# iron-hotplate.net
KiCad netlist of a schematic drawn in EAGLE
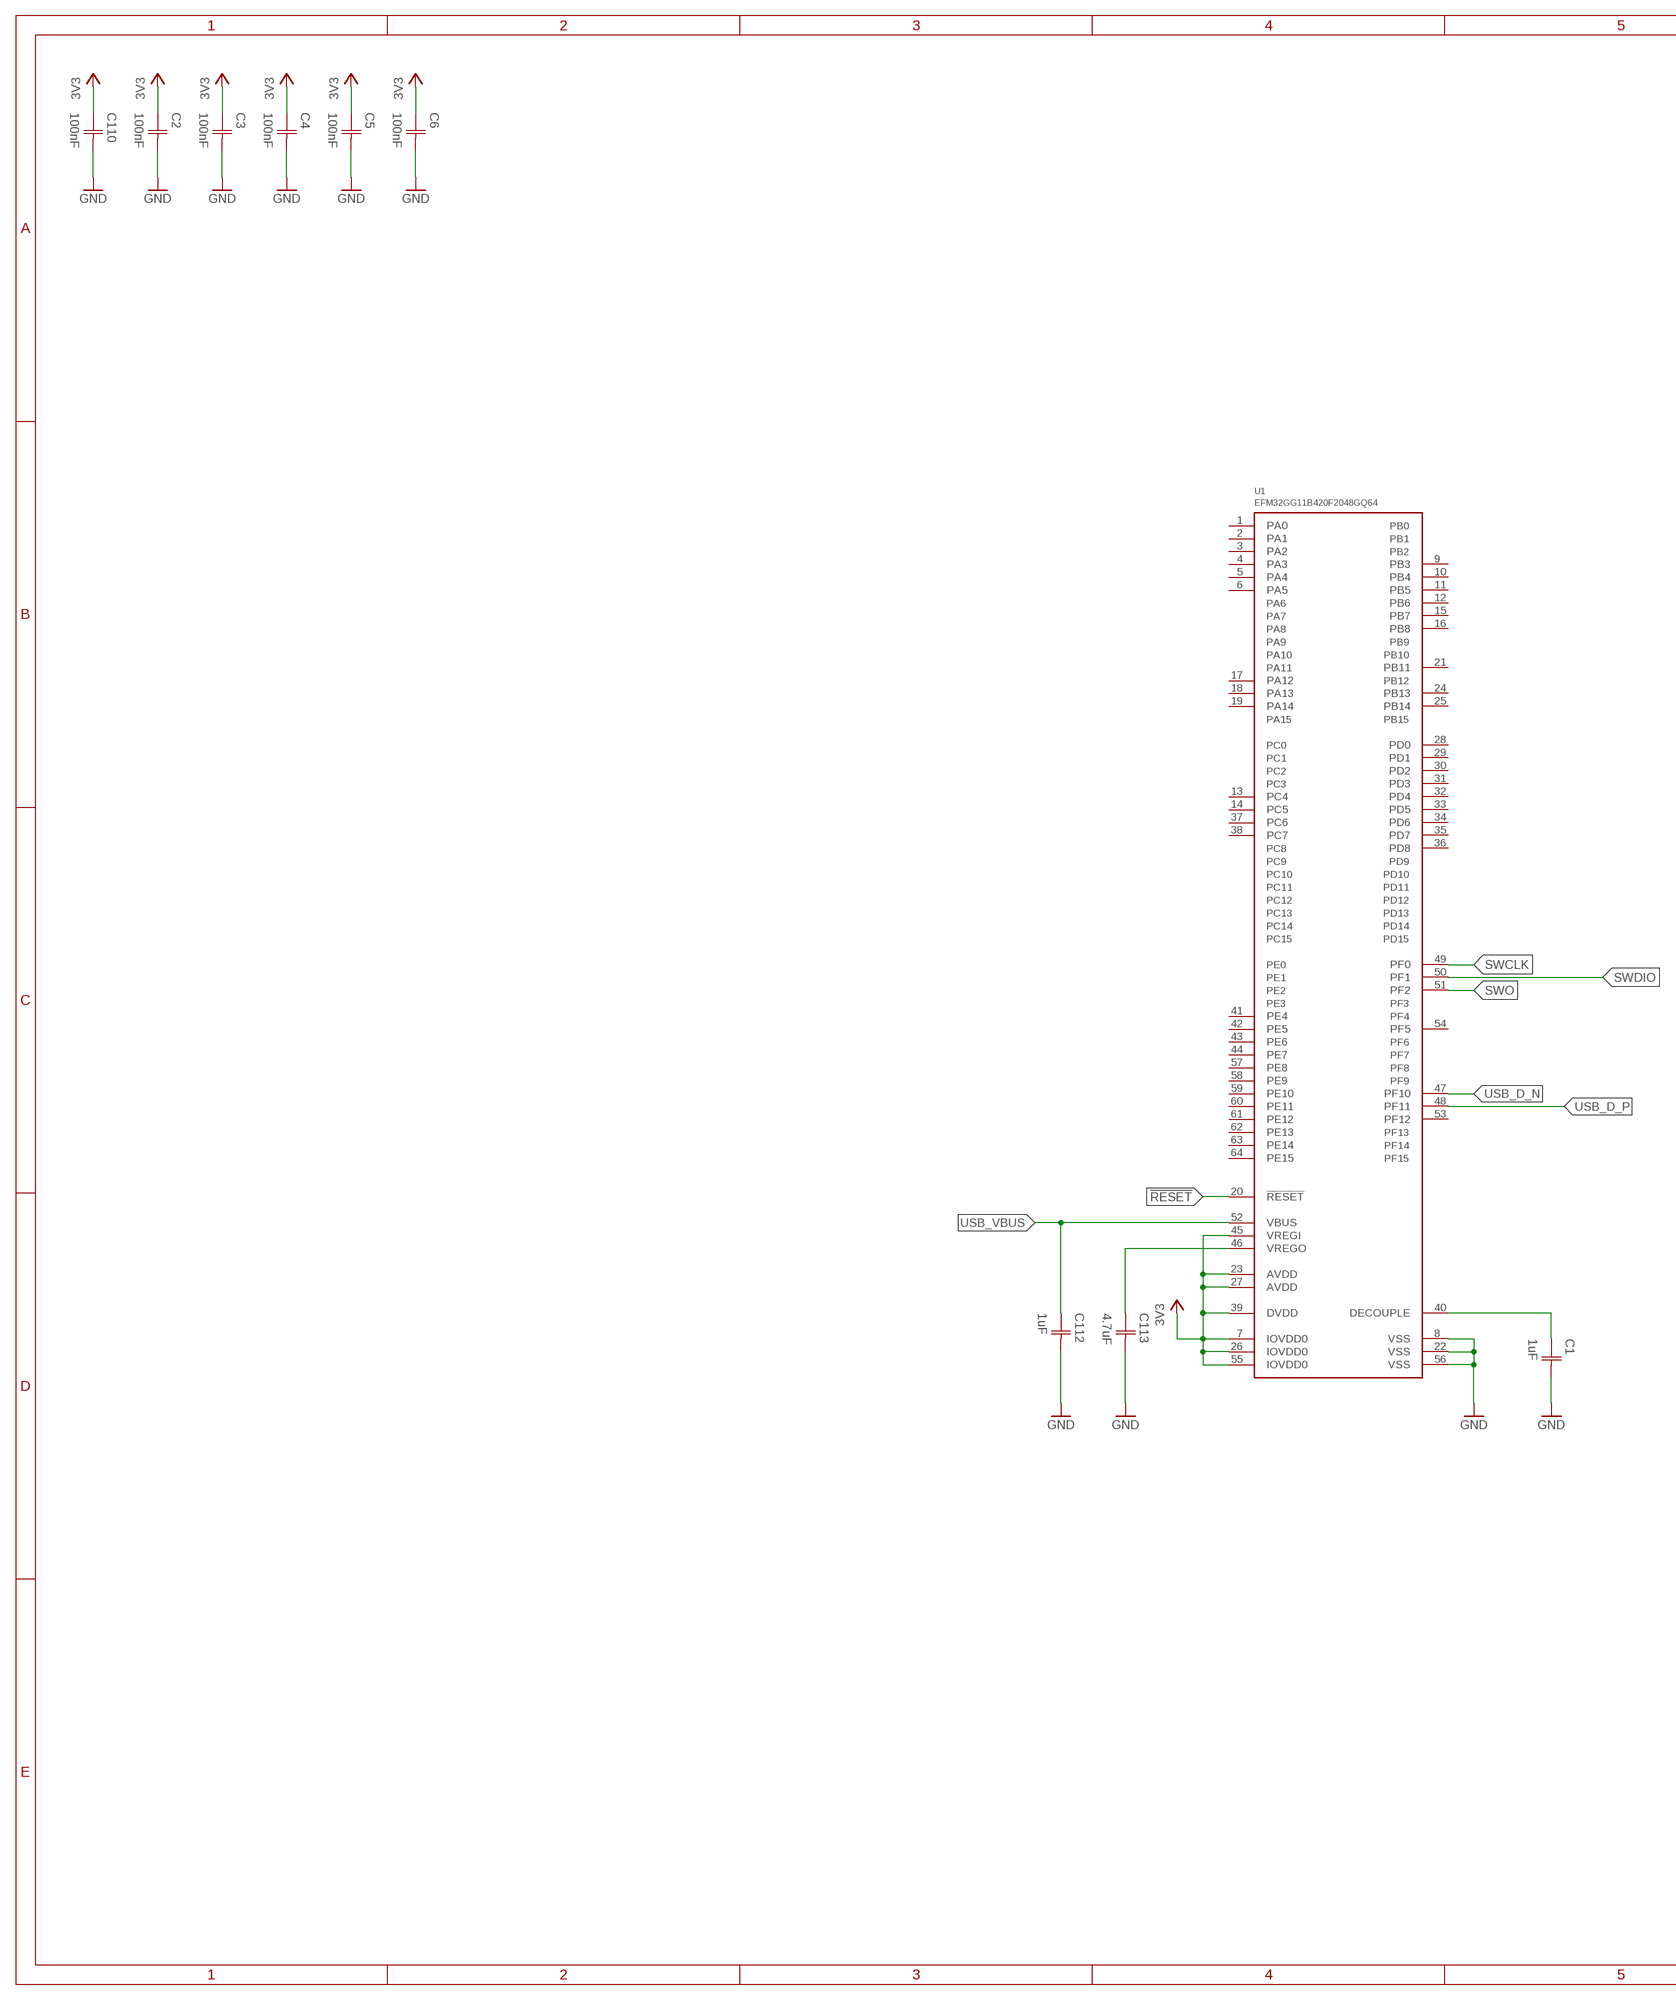
[diagram p0: schematic, sheet 1, part 1 of 2]
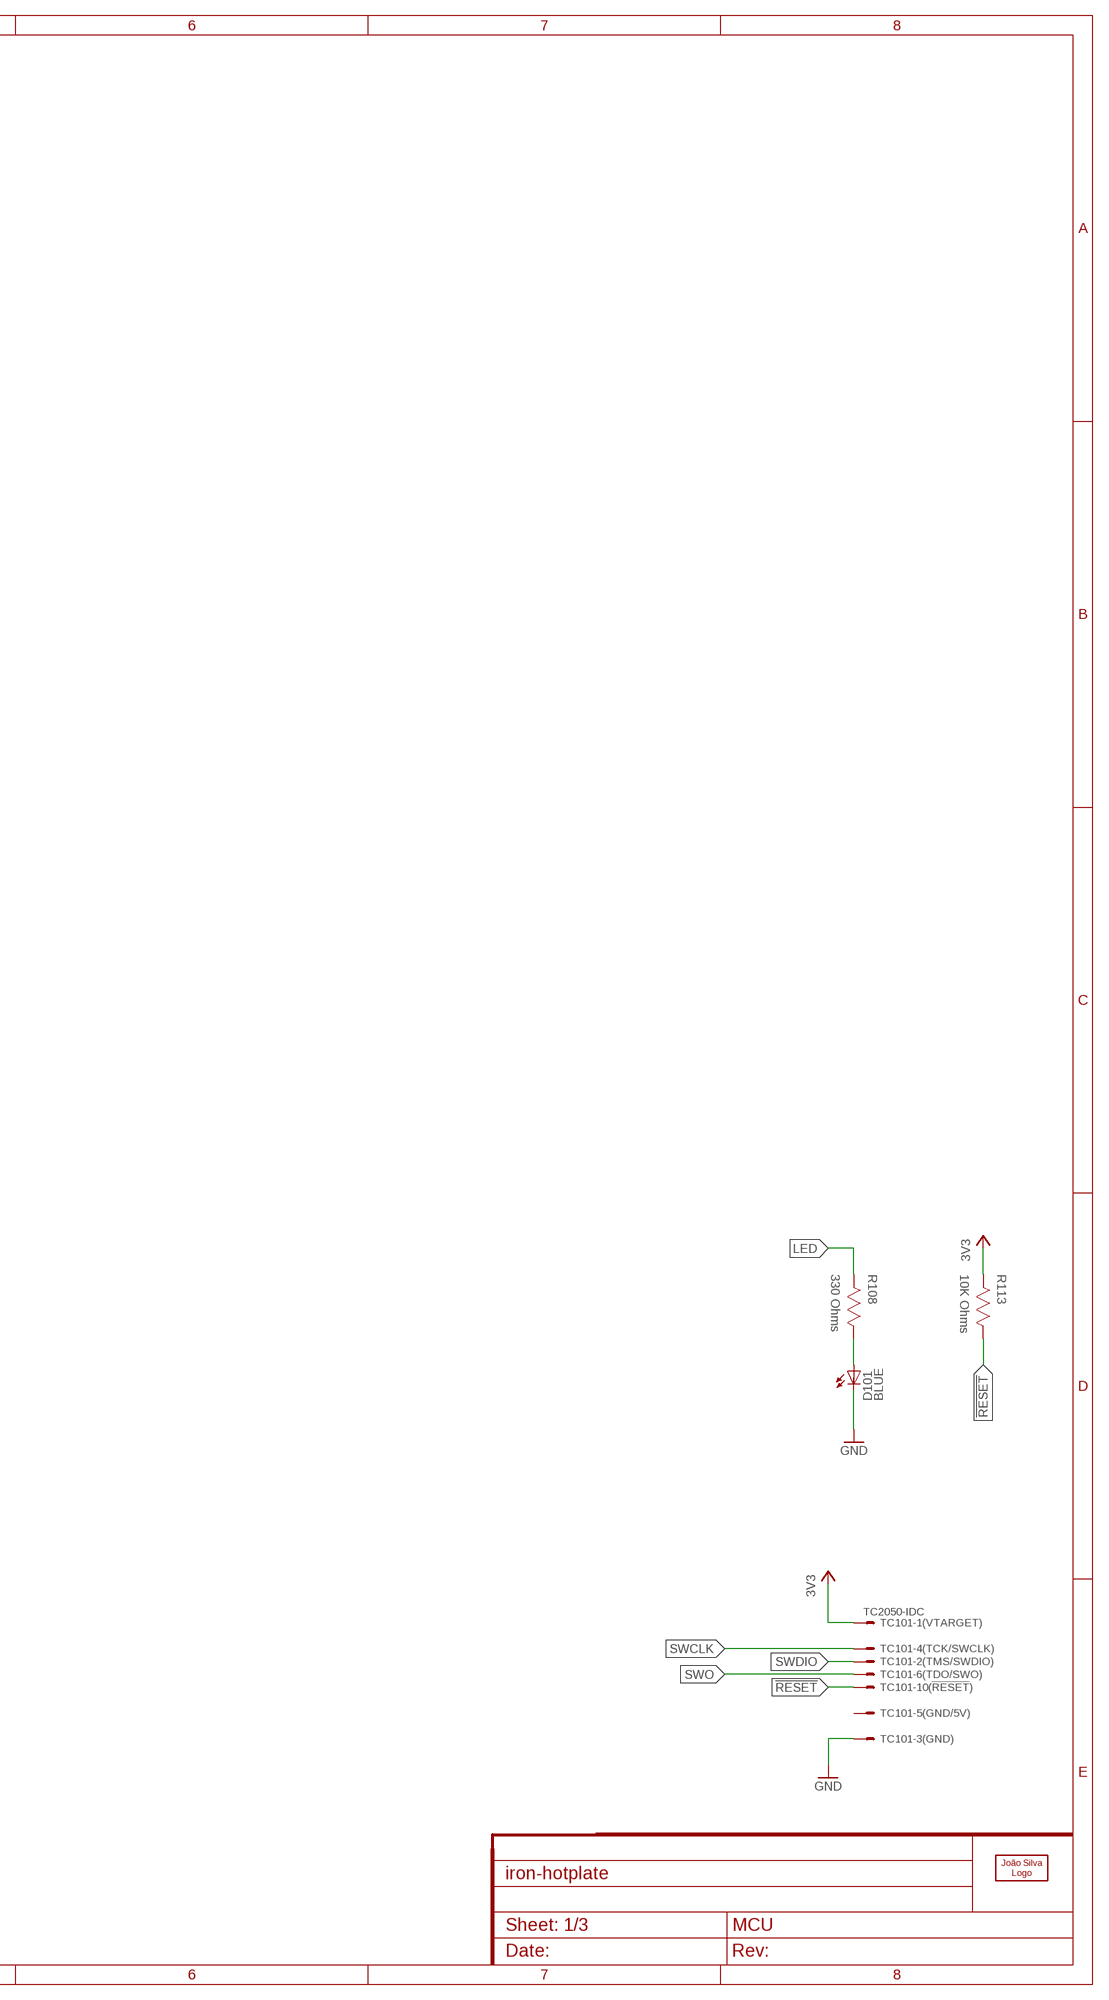
[diagram p1: schematic, sheet 1, part 2 of 2]
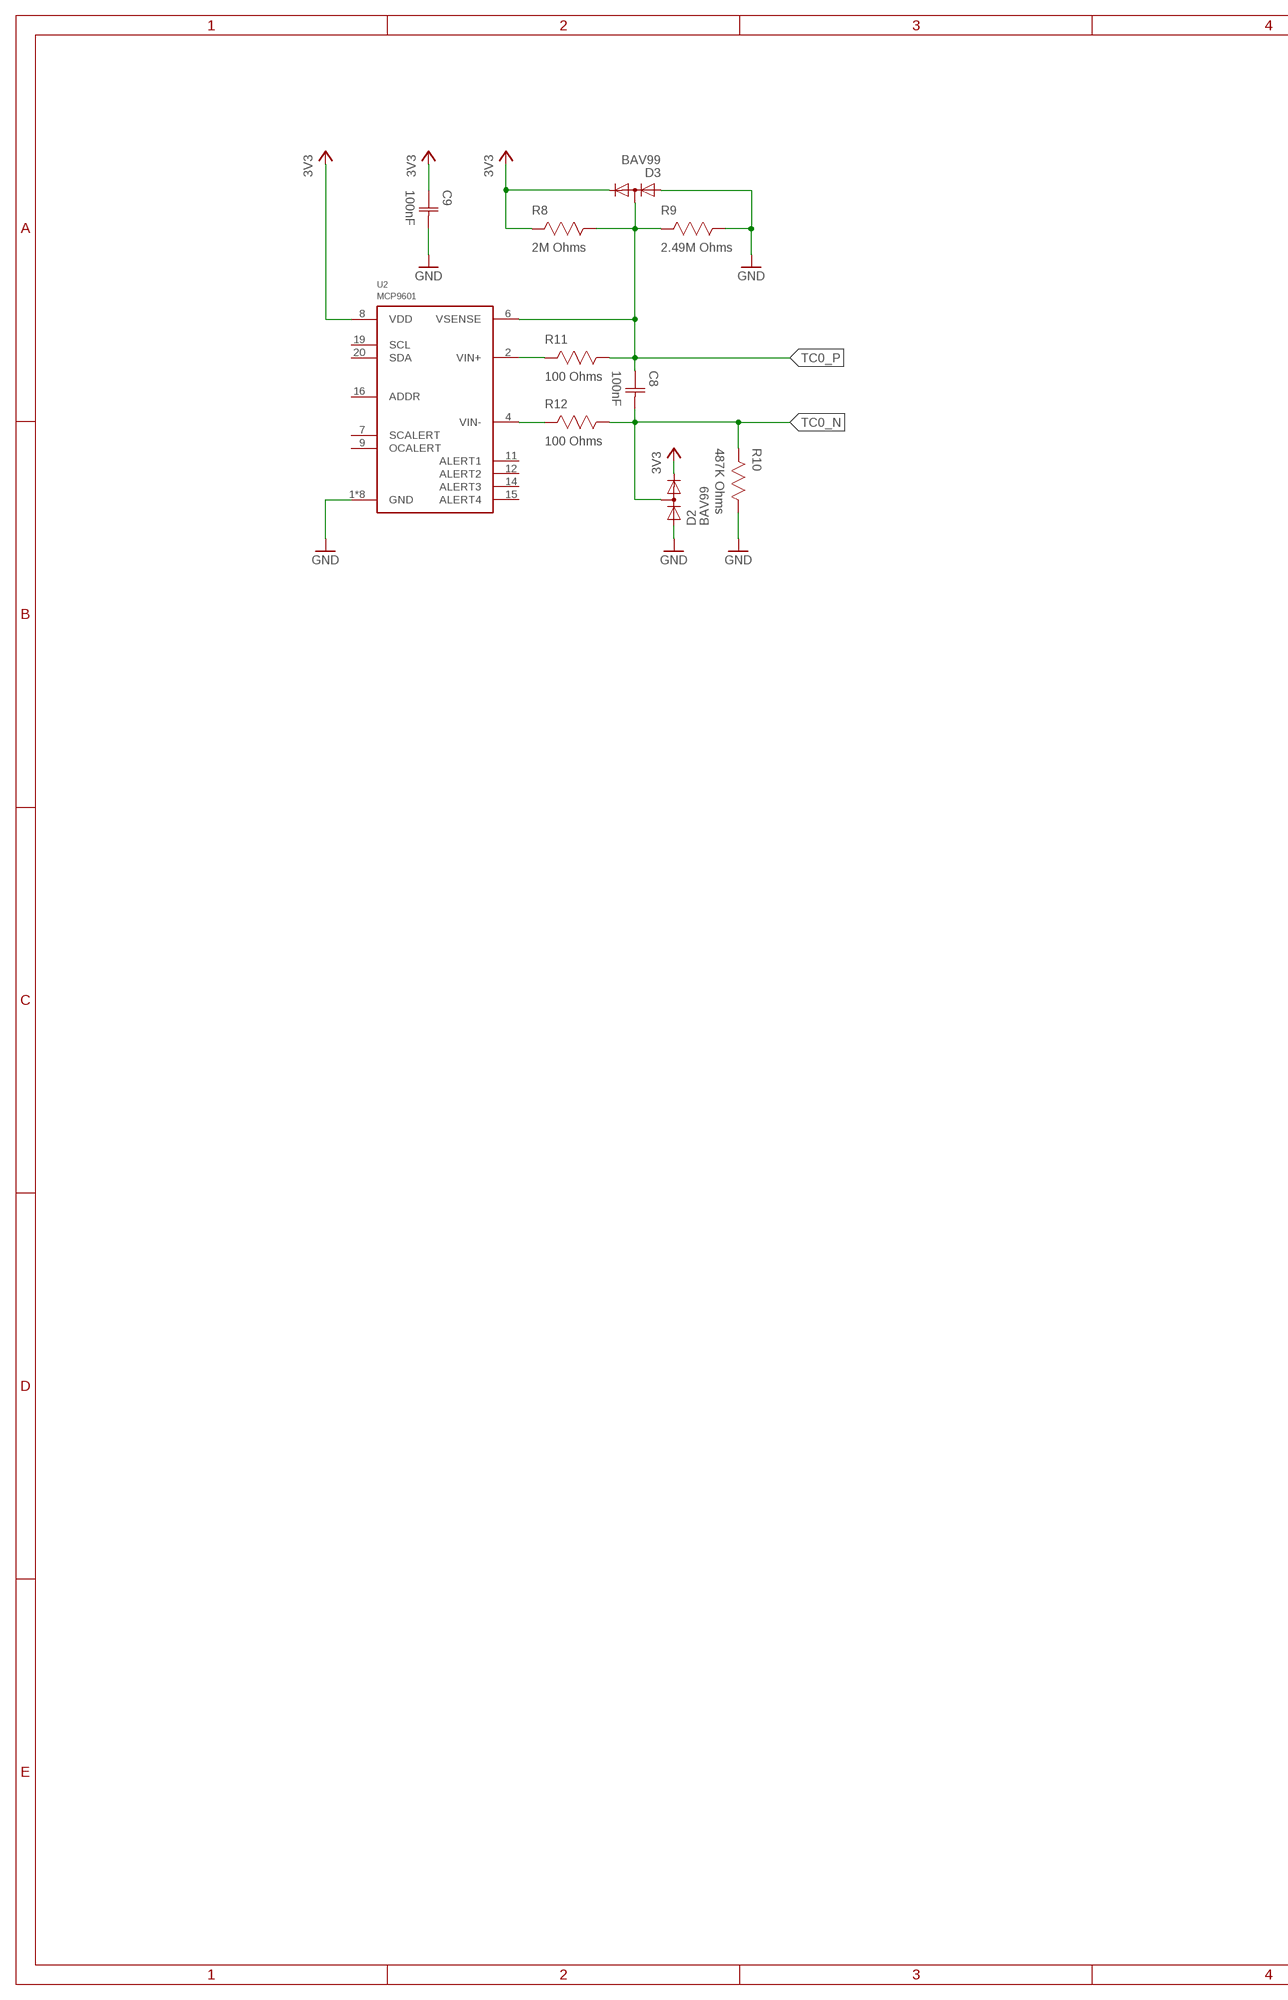
[diagram p2: schematic, sheet 2, part 1 of 2]
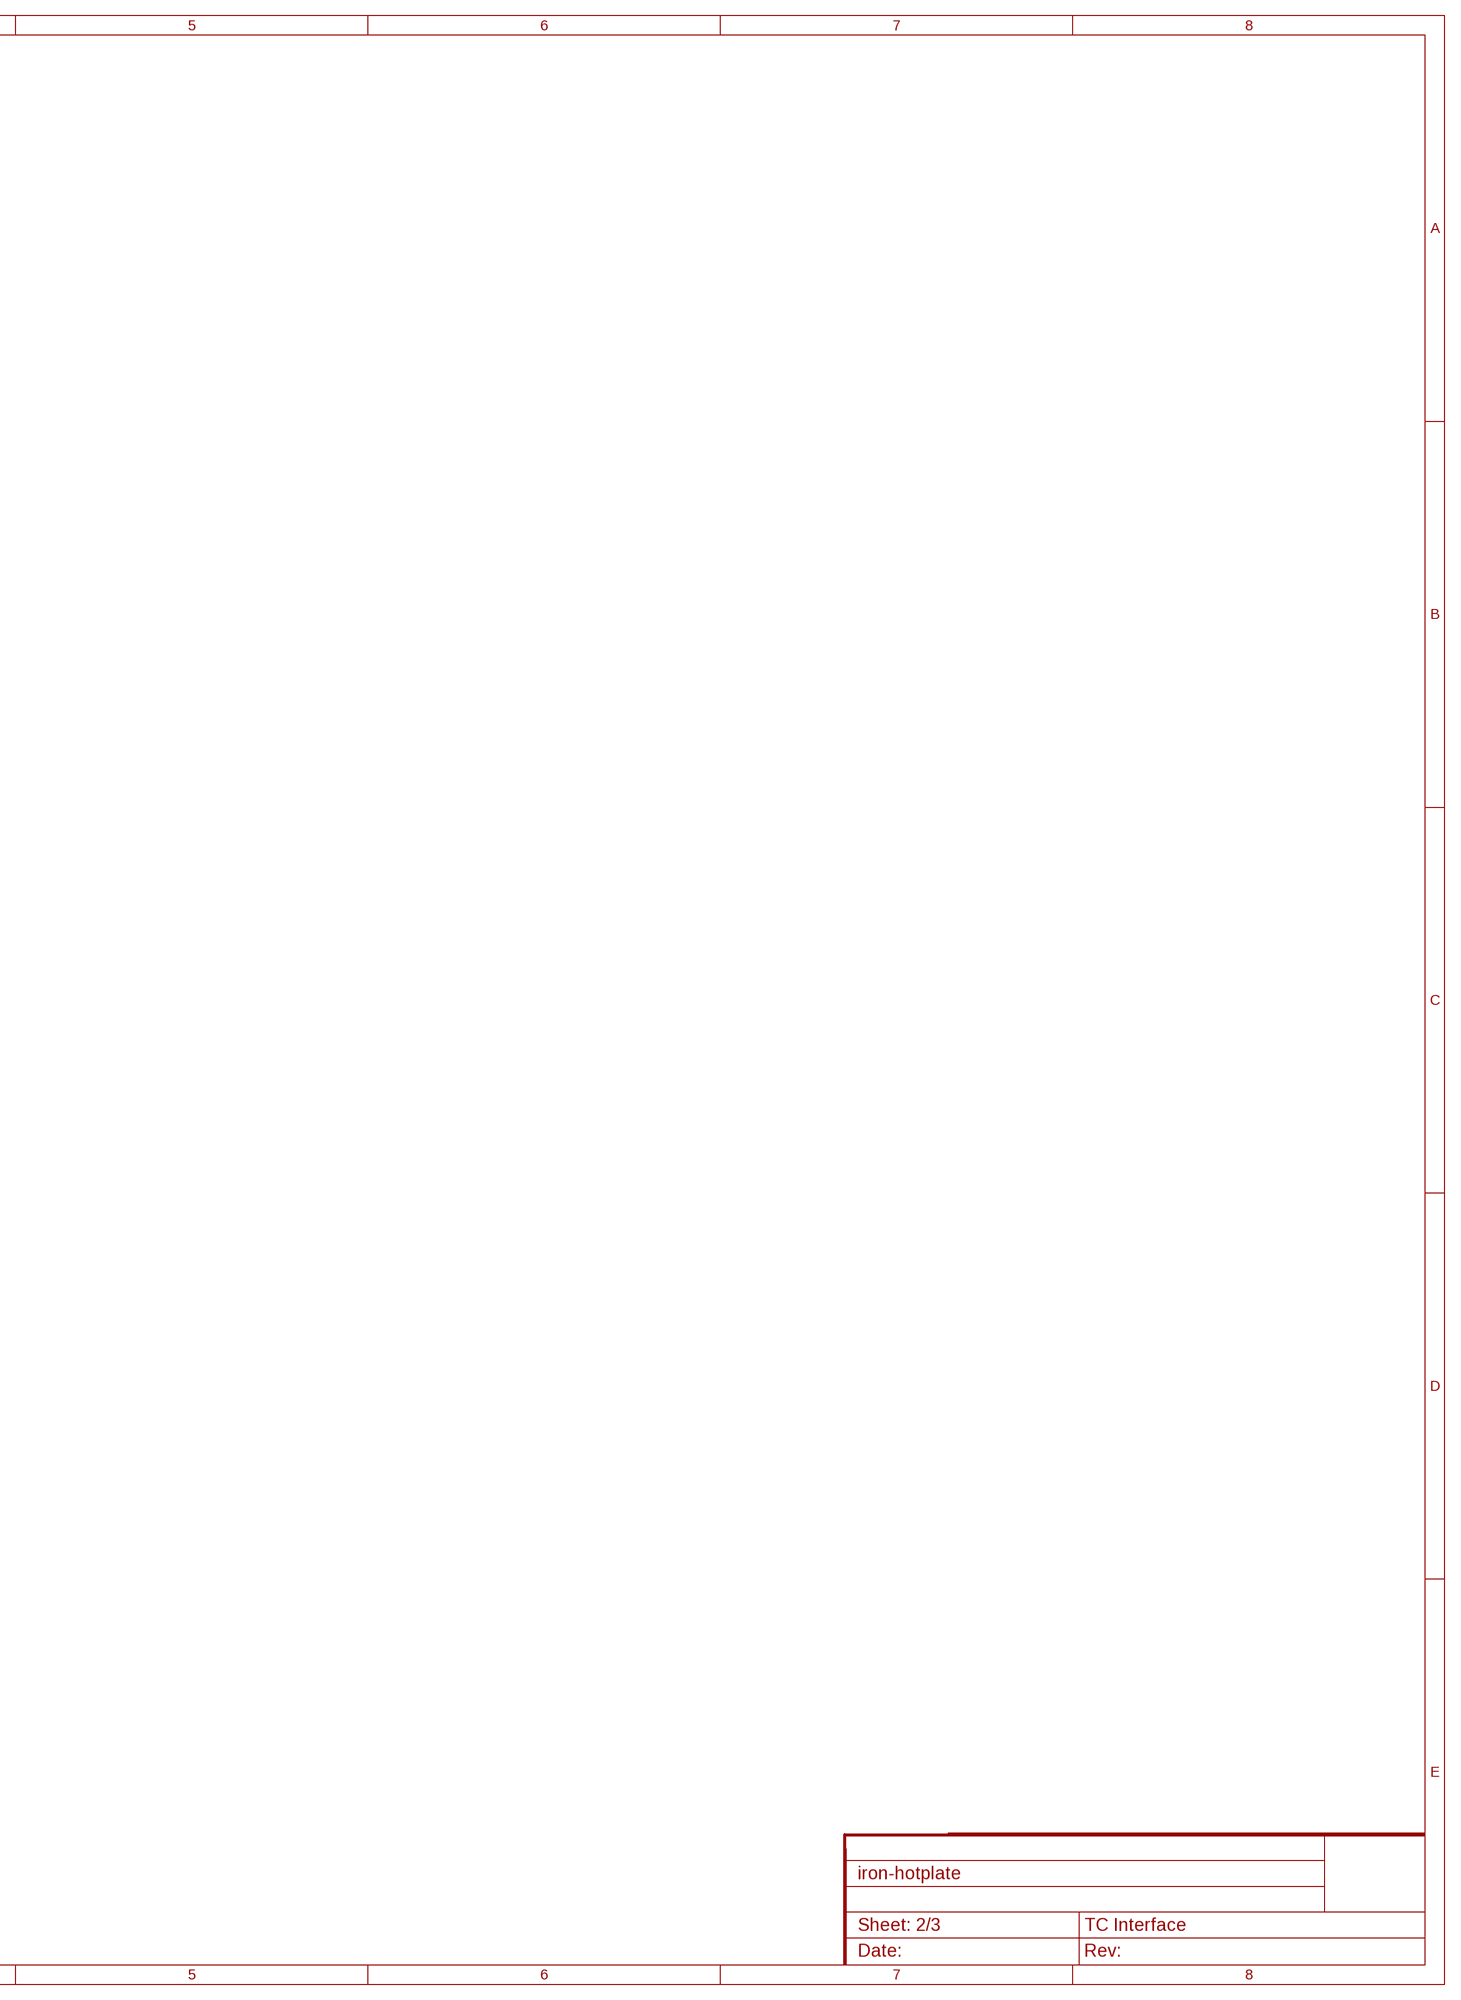
[diagram p3: schematic, sheet 2, part 2 of 2]
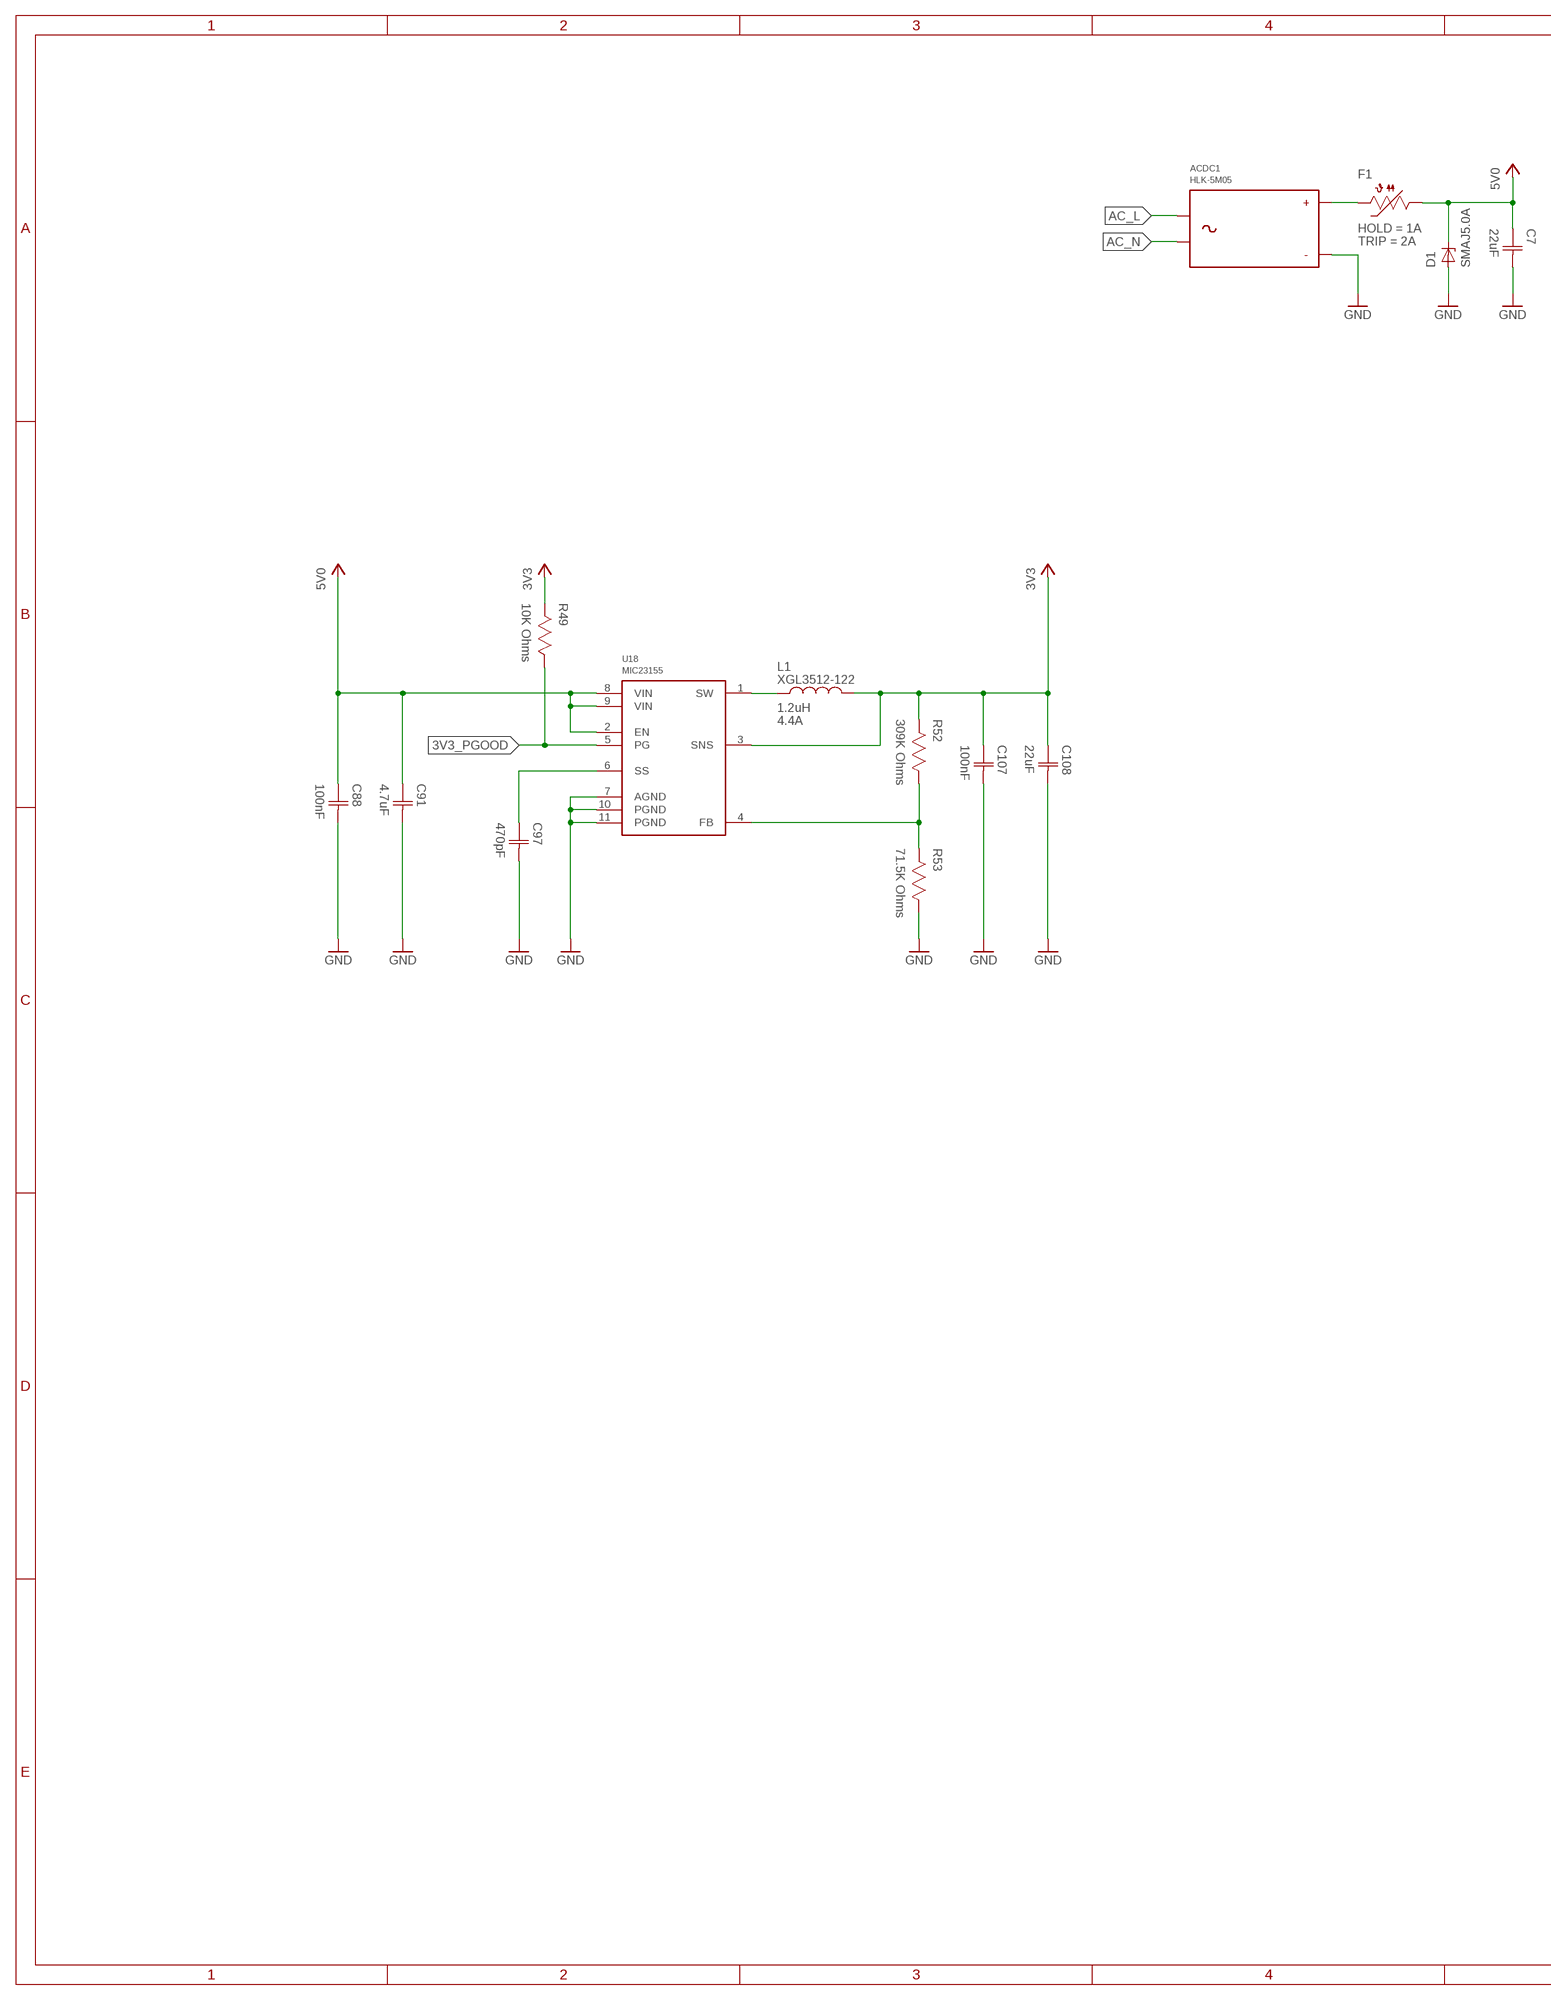
[diagram p4: schematic, sheet 3, part 1 of 2]
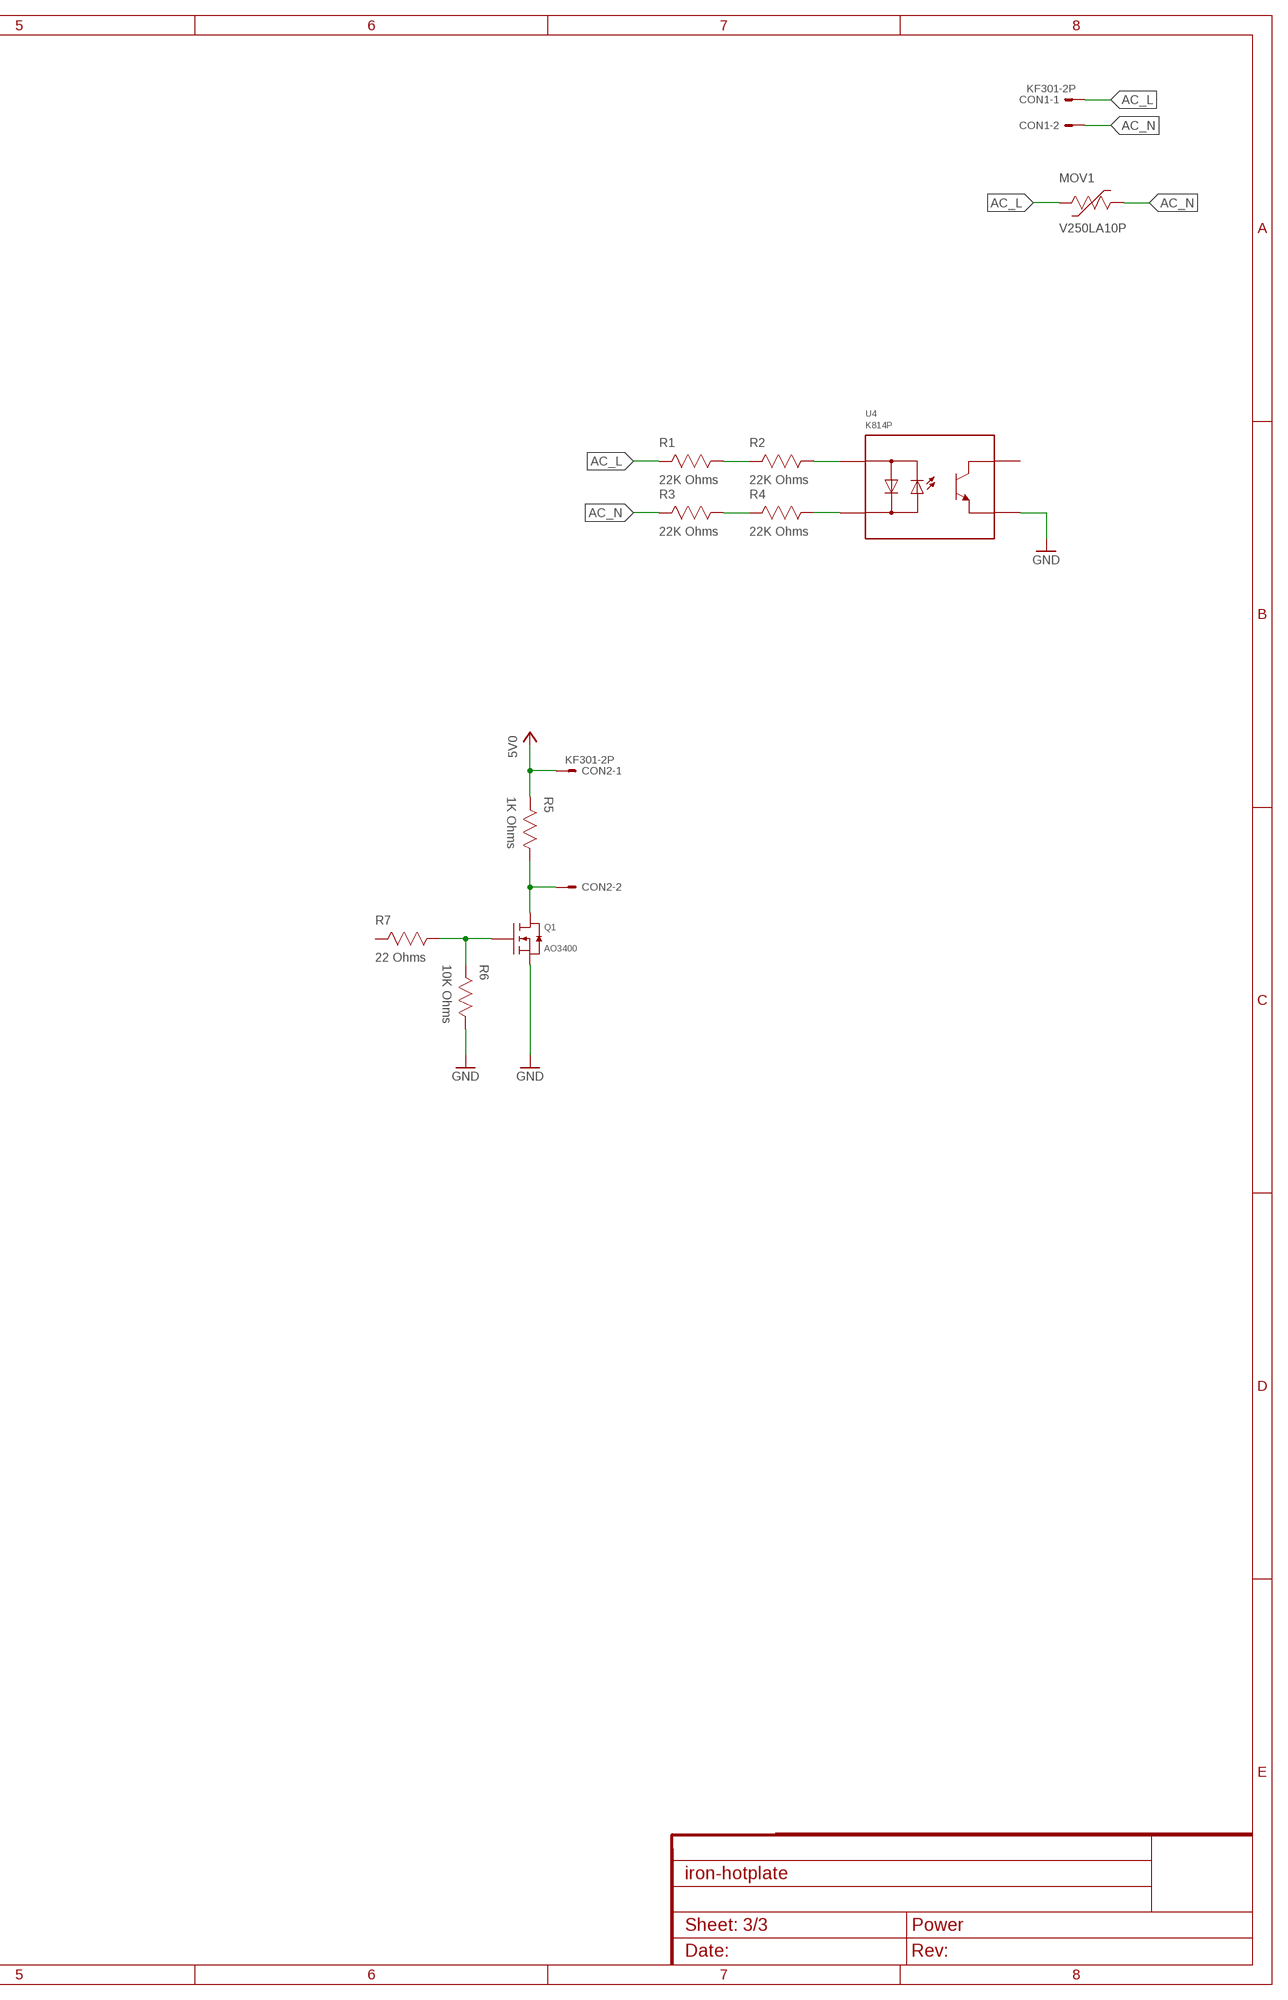
[diagram p5: schematic, sheet 3, part 2 of 2]

(export (version "E")
  (design (tool "Eeschema 10.0.6"))
  (components
    (comp (ref "C1")
      (value "1uF")
      (footprint "eagle-import:CAP0402")
      (libsource (lib "eagle-import") (part "CAPACITOR-0402"))
    )
    (comp (ref "C2")
      (value "100nF")
      (footprint "eagle-import:CAP0402")
      (libsource (lib "eagle-import") (part "CAPACITOR-0402"))
    )
    (comp (ref "C3")
      (value "100nF")
      (footprint "eagle-import:CAP0402")
      (libsource (lib "eagle-import") (part "CAPACITOR-0402"))
    )
    (comp (ref "C4")
      (value "100nF")
      (footprint "eagle-import:CAP0402")
      (libsource (lib "eagle-import") (part "CAPACITOR-0402"))
    )
    (comp (ref "C5")
      (value "100nF")
      (footprint "eagle-import:CAP0402")
      (libsource (lib "eagle-import") (part "CAPACITOR-0402"))
    )
    (comp (ref "C6")
      (value "100nF")
      (footprint "eagle-import:CAP0402")
      (libsource (lib "eagle-import") (part "CAPACITOR-0402"))
    )
    (comp (ref "C110")
      (value "100nF")
      (footprint "eagle-import:CAP0402")
      (libsource (lib "eagle-import") (part "CAPACITOR-0402"))
    )
    (comp (ref "C112")
      (value "1uF")
      (footprint "eagle-import:CAP0402")
      (libsource (lib "eagle-import") (part "CAPACITOR-0402"))
    )
    (comp (ref "C113")
      (value "4.7uF")
      (footprint "eagle-import:CAP0603")
      (libsource (lib "eagle-import") (part "CAPACITOR-0603"))
    )
    (comp (ref "D101")
      (value "LED0603")
      (footprint "eagle-import:0603")
      (fields (field (name "COLOR") "BLUE"))
      (libsource (lib "eagle-import") (part "LED0603"))
    )
    (comp (ref "LOGO1")
      (value "JS-5MM")
      (footprint "eagle-import:JS_5MM")
      (libsource (lib "eagle-import") (part "JS-5MM"))
    )
    (comp (ref "R108")
      (value "330 Ohms")
      (footprint "eagle-import:RES0402")
      (libsource (lib "eagle-import") (part "RESISTOR-0402"))
    )
    (comp (ref "R113")
      (value "10K Ohms")
      (footprint "eagle-import:RES0402")
      (libsource (lib "eagle-import") (part "RESISTOR-0402"))
    )
    (comp (ref "TC101")
      (value "TC2050-IDC")
      (footprint "eagle-import:TC2050-IDC")
      (libsource (lib "eagle-import") (part "TC2050-IDC"))
    )
    (comp (ref "U1")
      (value "EFM32GG11B420F2048GQ64")
      (footprint "eagle-import:QFP64")
      (libsource (lib "eagle-import") (part "EFM32GG11B4Q6420F2048G"))
    )
    (comp (ref "ACDC1")
      (value "HLK-5M05")
      (footprint "eagle-import:HLK-5M05")
      (libsource (lib "eagle-import") (part "HLK-5M05"))
    )
    (comp (ref "C7")
      (value "22uF")
      (footprint "eagle-import:CAP1206")
      (libsource (lib "eagle-import") (part "CAPACITOR-1206"))
    )
    (comp (ref "C88")
      (value "100nF")
      (footprint "eagle-import:CAP0402")
      (libsource (lib "eagle-import") (part "CAPACITOR-0402"))
    )
    (comp (ref "C91")
      (value "4.7uF")
      (footprint "eagle-import:CAP0603")
      (libsource (lib "eagle-import") (part "CAPACITOR-0603"))
    )
    (comp (ref "C97")
      (value "470pF")
      (footprint "eagle-import:CAP0402")
      (libsource (lib "eagle-import") (part "CAPACITOR-0402"))
    )
    (comp (ref "C107")
      (value "100nF")
      (footprint "eagle-import:CAP0402")
      (libsource (lib "eagle-import") (part "CAPACITOR-0402"))
    )
    (comp (ref "C108")
      (value "22uF")
      (footprint "eagle-import:CAP1206")
      (libsource (lib "eagle-import") (part "CAPACITOR-1206"))
    )
    (comp (ref "CON1")
      (value "KF301-2P")
      (footprint "eagle-import:KF301-2P")
      (libsource (lib "eagle-import") (part "KF301-2P"))
    )
    (comp (ref "CON2")
      (value "KF301-2P")
      (footprint "eagle-import:KF301-2P")
      (libsource (lib "eagle-import") (part "KF301-2P"))
    )
    (comp (ref "D1")
      (value "SMAJ5.0A")
      (footprint "eagle-import:DO214AC")
      (fields (field (name "MF") "Littelfuse"))
      (libsource (lib "eagle-import") (part "SMAJA5.0"))
    )
    (comp (ref "F1")
      (value "PTC1206")
      (footprint "eagle-import:1206")
      (fields (field (name "HOLD") "1A") (field (name "TRIP") "2A"))
      (libsource (lib "eagle-import") (part "PTC1206"))
    )
    (comp (ref "L1")
      (value "1.2uH")
      (footprint "eagle-import:XGL351X")
      (fields (field (name "CURRENT") "4.4A") (field (name "REF") "XGL3512-122"))
      (libsource (lib "eagle-import") (part "XGL3512-122"))
    )
    (comp (ref "MOV1")
      (value "V250LA10P")
      (footprint "eagle-import:VXXXLA10P")
      (libsource (lib "eagle-import") (part "V250LA10P"))
    )
    (comp (ref "Q1")
      (value "AO3400")
      (footprint "eagle-import:SOT23")
      (libsource (lib "eagle-import") (part "AO3400"))
    )
    (comp (ref "R1")
      (value "22K Ohms")
      (footprint "eagle-import:RES1206")
      (libsource (lib "eagle-import") (part "RESISTOR-1206"))
    )
    (comp (ref "R2")
      (value "22K Ohms")
      (footprint "eagle-import:RES1206")
      (libsource (lib "eagle-import") (part "RESISTOR-1206"))
    )
    (comp (ref "R3")
      (value "22K Ohms")
      (footprint "eagle-import:RES1206")
      (libsource (lib "eagle-import") (part "RESISTOR-1206"))
    )
    (comp (ref "R4")
      (value "22K Ohms")
      (footprint "eagle-import:RES1206")
      (libsource (lib "eagle-import") (part "RESISTOR-1206"))
    )
    (comp (ref "R5")
      (value "1K Ohms")
      (footprint "eagle-import:RES0402")
      (libsource (lib "eagle-import") (part "RESISTOR-0402"))
    )
    (comp (ref "R6")
      (value "10K Ohms")
      (footprint "eagle-import:RES0402")
      (libsource (lib "eagle-import") (part "RESISTOR-0402"))
    )
    (comp (ref "R7")
      (value "22 Ohms")
      (footprint "eagle-import:RES0402")
      (libsource (lib "eagle-import") (part "RESISTOR-0402"))
    )
    (comp (ref "R49")
      (value "10K Ohms")
      (footprint "eagle-import:RES0402")
      (libsource (lib "eagle-import") (part "RESISTOR-0402"))
    )
    (comp (ref "R52")
      (value "309K Ohms")
      (footprint "eagle-import:RES0402")
      (libsource (lib "eagle-import") (part "RESISTOR-0402"))
    )
    (comp (ref "R53")
      (value "71.5K Ohms")
      (footprint "eagle-import:RES0402")
      (libsource (lib "eagle-import") (part "RESISTOR-0402"))
    )
    (comp (ref "U4")
      (value "K814P")
      (footprint "eagle-import:DIP_2.54")
      (libsource (lib "eagle-import") (part "K814P"))
    )
    (comp (ref "U18")
      (value "MIC23155")
      (footprint "eagle-import:DFN10")
      (libsource (lib "eagle-import") (part "MIC23155"))
    )
    (comp (ref "C8")
      (value "100nF")
      (footprint "eagle-import:CAP0402")
      (libsource (lib "eagle-import") (part "CAPACITOR-0402"))
    )
    (comp (ref "C9")
      (value "100nF")
      (footprint "eagle-import:CAP0402")
      (libsource (lib "eagle-import") (part "CAPACITOR-0402"))
    )
    (comp (ref "D2")
      (value "BAV99")
      (footprint "eagle-import:SOT23")
      (libsource (lib "eagle-import") (part "BAV99"))
    )
    (comp (ref "D3")
      (value "BAV99")
      (footprint "eagle-import:SOT23")
      (libsource (lib "eagle-import") (part "BAV99"))
    )
    (comp (ref "R8")
      (value "2M Ohms")
      (footprint "eagle-import:RES0402")
      (libsource (lib "eagle-import") (part "RESISTOR-0402"))
    )
    (comp (ref "R9")
      (value "2.49M Ohms")
      (footprint "eagle-import:RES0402")
      (libsource (lib "eagle-import") (part "RESISTOR-0402"))
    )
    (comp (ref "R10")
      (value "487K Ohms")
      (footprint "eagle-import:RES0402")
      (libsource (lib "eagle-import") (part "RESISTOR-0402"))
    )
    (comp (ref "R11")
      (value "100 Ohms")
      (footprint "eagle-import:RES0402")
      (libsource (lib "eagle-import") (part "RESISTOR-0402"))
    )
    (comp (ref "R12")
      (value "100 Ohms")
      (footprint "eagle-import:RES0402")
      (libsource (lib "eagle-import") (part "RESISTOR-0402"))
    )
    (comp (ref "U2")
      (value "MCP9601")
      (footprint "eagle-import:MQFN20")
      (libsource (lib "eagle-import") (part "MCP9601"))
    )
  )
  (nets
    (net (code "1") (name "3V3") (class "Default")
      (node (ref "C107") (pin "1") (pinfunction "C1_1") (pintype "passive"))
      (node (ref "C108") (pin "1") (pinfunction "C1_1") (pintype "passive"))
      (node (ref "C110") (pin "1") (pinfunction "C1_1") (pintype "passive"))
      (node (ref "C2") (pin "1") (pinfunction "C1_1") (pintype "passive"))
      (node (ref "C3") (pin "1") (pinfunction "C1_1") (pintype "passive"))
      (node (ref "C4") (pin "1") (pinfunction "C1_1") (pintype "passive"))
      (node (ref "C5") (pin "1") (pinfunction "C1_1") (pintype "passive"))
      (node (ref "C6") (pin "1") (pinfunction "C1_1") (pintype "passive"))
      (node (ref "C9") (pin "1") (pinfunction "C1_1") (pintype "passive"))
      (node (ref "D2") (pin "2") (pinfunction "C_2") (pintype "passive"))
      (node (ref "D3") (pin "2") (pinfunction "C_2") (pintype "passive"))
      (node (ref "L1") (pin "2") (pinfunction "2_2") (pintype "passive"))
      (node (ref "R113") (pin "2") (pinfunction "2_2") (pintype "passive"))
      (node (ref "R49") (pin "2") (pinfunction "2_2") (pintype "passive"))
      (node (ref "R52") (pin "2") (pinfunction "2_2") (pintype "passive"))
      (node (ref "R8") (pin "2") (pinfunction "2_2") (pintype "passive"))
      (node (ref "TC101") (pin "1") (pinfunction "S_1") (pintype "passive"))
      (node (ref "U1") (pin "23") (pinfunction "AVDD_23") (pintype "bidirectional"))
      (node (ref "U1") (pin "26") (pinfunction "IOVDD0_26") (pintype "bidirectional"))
      (node (ref "U1") (pin "27") (pinfunction "AVDD_27") (pintype "bidirectional"))
      (node (ref "U1") (pin "39") (pinfunction "DVDD_39") (pintype "bidirectional"))
      (node (ref "U1") (pin "45") (pinfunction "VREGI_45") (pintype "bidirectional"))
      (node (ref "U1") (pin "55") (pinfunction "IOVDD0_55") (pintype "bidirectional"))
      (node (ref "U1") (pin "7") (pinfunction "IOVDD0_7") (pintype "bidirectional"))
      (node (ref "U18") (pin "3") (pinfunction "SNS_3") (pintype "bidirectional"))
      (node (ref "U2") (pin "8") (pinfunction "VDD_8") (pintype "bidirectional"))
    )
    (net (code "2") (name "3V3_PGOOD") (class "Default")
      (node (ref "R49") (pin "1") (pinfunction "1_1") (pintype "passive"))
      (node (ref "U18") (pin "5") (pinfunction "PG_5") (pintype "bidirectional"))
    )
    (net (code "3") (name "5V0") (class "Default")
      (node (ref "C7") (pin "1") (pinfunction "C1_1") (pintype "passive"))
      (node (ref "C88") (pin "1") (pinfunction "C1_1") (pintype "passive"))
      (node (ref "C91") (pin "1") (pinfunction "C1_1") (pintype "passive"))
      (node (ref "CON2") (pin "1") (pinfunction "S_1") (pintype "passive"))
      (node (ref "D1") (pin "C") (pinfunction "C_C") (pintype "passive"))
      (node (ref "F1") (pin "1") (pinfunction "1_1") (pintype "passive"))
      (node (ref "R5") (pin "2") (pinfunction "2_2") (pintype "passive"))
      (node (ref "U18") (pin "2") (pinfunction "EN_2") (pintype "bidirectional"))
      (node (ref "U18") (pin "8") (pinfunction "VIN_8") (pintype "bidirectional"))
      (node (ref "U18") (pin "9") (pinfunction "VIN_9") (pintype "bidirectional"))
    )
    (net (code "4") (name "AC_L") (class "Default")
      (node (ref "ACDC1") (pin "AC1") (pinfunction "AC1_AC1") (pintype "bidirectional"))
      (node (ref "CON1") (pin "1") (pinfunction "S_1") (pintype "passive"))
      (node (ref "MOV1") (pin "2") (pinfunction "2_2") (pintype "passive"))
      (node (ref "R1") (pin "2") (pinfunction "2_2") (pintype "passive"))
    )
    (net (code "5") (name "AC_N") (class "Default")
      (node (ref "ACDC1") (pin "AC2") (pinfunction "AC2_AC2") (pintype "bidirectional"))
      (node (ref "CON1") (pin "2") (pinfunction "S_2") (pintype "passive"))
      (node (ref "MOV1") (pin "1") (pinfunction "1_1") (pintype "passive"))
      (node (ref "R3") (pin "2") (pinfunction "2_2") (pintype "passive"))
    )
    (net (code "6") (name "GND") (class "Default")
      (node (ref "ACDC1") (pin "-VO") (pinfunction "-VO_-VO") (pintype "bidirectional"))
      (node (ref "C1") (pin "2") (pinfunction "C2_2") (pintype "passive"))
      (node (ref "C107") (pin "2") (pinfunction "C2_2") (pintype "passive"))
      (node (ref "C108") (pin "2") (pinfunction "C2_2") (pintype "passive"))
      (node (ref "C110") (pin "2") (pinfunction "C2_2") (pintype "passive"))
      (node (ref "C112") (pin "2") (pinfunction "C2_2") (pintype "passive"))
      (node (ref "C113") (pin "2") (pinfunction "C2_2") (pintype "passive"))
      (node (ref "C2") (pin "2") (pinfunction "C2_2") (pintype "passive"))
      (node (ref "C3") (pin "2") (pinfunction "C2_2") (pintype "passive"))
      (node (ref "C4") (pin "2") (pinfunction "C2_2") (pintype "passive"))
      (node (ref "C5") (pin "2") (pinfunction "C2_2") (pintype "passive"))
      (node (ref "C6") (pin "2") (pinfunction "C2_2") (pintype "passive"))
      (node (ref "C7") (pin "2") (pinfunction "C2_2") (pintype "passive"))
      (node (ref "C88") (pin "2") (pinfunction "C2_2") (pintype "passive"))
      (node (ref "C9") (pin "2") (pinfunction "C2_2") (pintype "passive"))
      (node (ref "C91") (pin "2") (pinfunction "C2_2") (pintype "passive"))
      (node (ref "C97") (pin "2") (pinfunction "C2_2") (pintype "passive"))
      (node (ref "D1") (pin "A") (pinfunction "A_A") (pintype "passive"))
      (node (ref "D101") (pin "C") (pinfunction "C_C") (pintype "passive"))
      (node (ref "D2") (pin "1") (pinfunction "A_1") (pintype "passive"))
      (node (ref "D3") (pin "1") (pinfunction "A_1") (pintype "passive"))
      (node (ref "Q1") (pin "2") (pinfunction "S_2") (pintype "passive"))
      (node (ref "R10") (pin "1") (pinfunction "1_1") (pintype "passive"))
      (node (ref "R53") (pin "1") (pinfunction "1_1") (pintype "passive"))
      (node (ref "R6") (pin "1") (pinfunction "1_1") (pintype "passive"))
      (node (ref "R9") (pin "1") (pinfunction "1_1") (pintype "passive"))
      (node (ref "TC101") (pin "3") (pinfunction "S_3") (pintype "passive"))
      (node (ref "U1") (pin "22") (pinfunction "VSS_22") (pintype "bidirectional"))
      (node (ref "U1") (pin "56") (pinfunction "VSS_56") (pintype "bidirectional"))
      (node (ref "U1") (pin "8") (pinfunction "VSS_8") (pintype "bidirectional"))
      (node (ref "U18") (pin "10") (pinfunction "PGND_10") (pintype "bidirectional"))
      (node (ref "U18") (pin "11") (pinfunction "PGND_11") (pintype "bidirectional"))
      (node (ref "U18") (pin "7") (pinfunction "AGND_7") (pintype "bidirectional"))
      (node (ref "U2") (pin "1") (pinfunction "GND_1") (pintype "bidirectional"))
      (node (ref "U2") (pin "10") (pinfunction "GND_10") (pintype "bidirectional"))
      (node (ref "U2") (pin "13") (pinfunction "GND_13") (pintype "bidirectional"))
      (node (ref "U2") (pin "17") (pinfunction "GND_17") (pintype "bidirectional"))
      (node (ref "U2") (pin "18") (pinfunction "GND_18") (pintype "bidirectional"))
      (node (ref "U2") (pin "3") (pinfunction "GND_3") (pintype "bidirectional"))
      (node (ref "U2") (pin "5") (pinfunction "GND_5") (pintype "bidirectional"))
      (node (ref "U2") (pin "EXP") (pinfunction "GND_EXP") (pintype "bidirectional"))
      (node (ref "U4") (pin "3") (pinfunction "E_3") (pintype "bidirectional"))
    )
    (net (code "7") (name "LED") (class "Default")
      (node (ref "R108") (pin "2") (pinfunction "2_2") (pintype "passive"))
    )
    (net (code "8") (name "Net-(ACDC1-Pad+VO)") (class "Default")
      (node (ref "ACDC1") (pin "+VO") (pinfunction "+VO_+VO") (pintype "bidirectional"))
      (node (ref "F1") (pin "2") (pinfunction "2_2") (pintype "passive"))
    )
    (net (code "9") (name "Net-(C1-C1)") (class "Default")
      (node (ref "C1") (pin "1") (pinfunction "C1_1") (pintype "passive"))
      (node (ref "U1") (pin "40") (pinfunction "DECOUPLE_40") (pintype "bidirectional"))
    )
    (net (code "10") (name "Net-(C97-C1)") (class "Default")
      (node (ref "C97") (pin "1") (pinfunction "C1_1") (pintype "passive"))
      (node (ref "U18") (pin "6") (pinfunction "SS_6") (pintype "bidirectional"))
    )
    (net (code "11") (name "Net-(C113-C1)") (class "Default")
      (node (ref "C113") (pin "1") (pinfunction "C1_1") (pintype "passive"))
      (node (ref "U1") (pin "46") (pinfunction "VREGO_46") (pintype "bidirectional"))
    )
    (net (code "12") (name "Net-(CON2B-S)") (class "Default")
      (node (ref "CON2") (pin "2") (pinfunction "S_2") (pintype "passive"))
      (node (ref "Q1") (pin "3") (pinfunction "D_3") (pintype "passive"))
      (node (ref "R5") (pin "1") (pinfunction "1_1") (pintype "passive"))
    )
    (net (code "13") (name "Net-(D101-PadA)") (class "Default")
      (node (ref "D101") (pin "A") (pinfunction "A_A") (pintype "passive"))
      (node (ref "R108") (pin "1") (pinfunction "1_1") (pintype "passive"))
    )
    (net (code "14") (name "Net-(Q1-G)") (class "Default")
      (node (ref "Q1") (pin "1") (pinfunction "G_1") (pintype "passive"))
      (node (ref "R6") (pin "2") (pinfunction "2_2") (pintype "passive"))
      (node (ref "R7") (pin "1") (pinfunction "1_1") (pintype "passive"))
    )
    (net (code "15") (name "Net-(R1-Pad1)") (class "Default")
      (node (ref "R1") (pin "1") (pinfunction "1_1") (pintype "passive"))
      (node (ref "R2") (pin "2") (pinfunction "2_2") (pintype "passive"))
    )
    (net (code "16") (name "Net-(R3-Pad1)") (class "Default")
      (node (ref "R3") (pin "1") (pinfunction "1_1") (pintype "passive"))
      (node (ref "R4") (pin "2") (pinfunction "2_2") (pintype "passive"))
    )
    (net (code "17") (name "Net-(U2-VIN+)") (class "Default")
      (node (ref "R11") (pin "2") (pinfunction "2_2") (pintype "passive"))
      (node (ref "U2") (pin "2") (pinfunction "VIN+_2") (pintype "bidirectional"))
    )
    (net (code "18") (name "Net-(U2-VIN-)") (class "Default")
      (node (ref "R12") (pin "2") (pinfunction "2_2") (pintype "passive"))
      (node (ref "U2") (pin "4") (pinfunction "VIN-_4") (pintype "bidirectional"))
    )
    (net (code "19") (name "Net-(U4-LED1)") (class "Default")
      (node (ref "R2") (pin "1") (pinfunction "1_1") (pintype "passive"))
      (node (ref "U4") (pin "1") (pinfunction "LED1_1") (pintype "bidirectional"))
    )
    (net (code "20") (name "Net-(U4-LED2)") (class "Default")
      (node (ref "R4") (pin "1") (pinfunction "1_1") (pintype "passive"))
      (node (ref "U4") (pin "2") (pinfunction "LED2_2") (pintype "bidirectional"))
    )
    (net (code "21") (name "Net-(U18-FB)") (class "Default")
      (node (ref "R52") (pin "1") (pinfunction "1_1") (pintype "passive"))
      (node (ref "R53") (pin "2") (pinfunction "2_2") (pintype "passive"))
      (node (ref "U18") (pin "4") (pinfunction "FB_4") (pintype "bidirectional"))
    )
    (net (code "22") (name "Net-(U18-SW)") (class "Default")
      (node (ref "L1") (pin "1") (pinfunction "1_1") (pintype "passive"))
      (node (ref "U18") (pin "1") (pinfunction "SW_1") (pintype "bidirectional"))
    )
    (net (code "23") (name "SWCLK") (class "Default")
      (node (ref "TC101") (pin "4") (pinfunction "S_4") (pintype "passive"))
      (node (ref "U1") (pin "49") (pinfunction "PF0_49") (pintype "bidirectional"))
    )
    (net (code "24") (name "SWDIO") (class "Default")
      (node (ref "TC101") (pin "2") (pinfunction "S_2") (pintype "passive"))
      (node (ref "U1") (pin "50") (pinfunction "PF1_50") (pintype "bidirectional"))
    )
    (net (code "25") (name "SWO") (class "Default")
      (node (ref "TC101") (pin "6") (pinfunction "S_6") (pintype "passive"))
      (node (ref "U1") (pin "51") (pinfunction "PF2_51") (pintype "bidirectional"))
    )
    (net (code "26") (name "TC0_N") (class "Default")
      (node (ref "C8") (pin "2") (pinfunction "C2_2") (pintype "passive"))
      (node (ref "D2") (pin "3") (pinfunction "MID_3") (pintype "passive"))
      (node (ref "R10") (pin "2") (pinfunction "2_2") (pintype "passive"))
      (node (ref "R12") (pin "1") (pinfunction "1_1") (pintype "passive"))
    )
    (net (code "27") (name "TC0_P") (class "Default")
      (node (ref "C8") (pin "1") (pinfunction "C1_1") (pintype "passive"))
      (node (ref "D3") (pin "3") (pinfunction "MID_3") (pintype "passive"))
      (node (ref "R11") (pin "1") (pinfunction "1_1") (pintype "passive"))
      (node (ref "R8") (pin "1") (pinfunction "1_1") (pintype "passive"))
      (node (ref "R9") (pin "2") (pinfunction "2_2") (pintype "passive"))
      (node (ref "U2") (pin "6") (pinfunction "VSENSE_6") (pintype "bidirectional"))
    )
    (net (code "28") (name "USB_D_N") (class "Default")
      (node (ref "U1") (pin "47") (pinfunction "PF10_47") (pintype "bidirectional"))
    )
    (net (code "29") (name "USB_D_P") (class "Default")
      (node (ref "U1") (pin "48") (pinfunction "PF11_48") (pintype "bidirectional"))
    )
    (net (code "30") (name "USB_VBUS") (class "Default")
      (node (ref "C112") (pin "1") (pinfunction "C1_1") (pintype "passive"))
      (node (ref "U1") (pin "52") (pinfunction "VBUS_52") (pintype "bidirectional"))
    )
    (net (code "31") (name "unconnected-(R7-Pad2)") (class "Default")
      (node (ref "R7") (pin "2") (pinfunction "2_2") (pintype "passive"))
    )
    (net (code "32") (name "unconnected-(TC101F-S-Pad5)") (class "Default")
      (node (ref "TC101") (pin "5") (pinfunction "S_5") (pintype "passive"))
    )
    (net (code "33") (name "unconnected-(U1-PA0-Pad1)") (class "Default")
      (node (ref "U1") (pin "1") (pinfunction "PA0_1") (pintype "bidirectional"))
    )
    (net (code "34") (name "unconnected-(U1-PA1-Pad2)") (class "Default")
      (node (ref "U1") (pin "2") (pinfunction "PA1_2") (pintype "bidirectional"))
    )
    (net (code "35") (name "unconnected-(U1-PA2-Pad3)") (class "Default")
      (node (ref "U1") (pin "3") (pinfunction "PA2_3") (pintype "bidirectional"))
    )
    (net (code "36") (name "unconnected-(U1-PA3-Pad4)") (class "Default")
      (node (ref "U1") (pin "4") (pinfunction "PA3_4") (pintype "bidirectional"))
    )
    (net (code "37") (name "unconnected-(U1-PA4-Pad5)") (class "Default")
      (node (ref "U1") (pin "5") (pinfunction "PA4_5") (pintype "bidirectional"))
    )
    (net (code "38") (name "unconnected-(U1-PA5-Pad6)") (class "Default")
      (node (ref "U1") (pin "6") (pinfunction "PA5_6") (pintype "bidirectional"))
    )
    (net (code "39") (name "unconnected-(U1-PA12-Pad17)") (class "Default")
      (node (ref "U1") (pin "17") (pinfunction "PA12_17") (pintype "bidirectional"))
    )
    (net (code "40") (name "unconnected-(U1-PA13-Pad18)") (class "Default")
      (node (ref "U1") (pin "18") (pinfunction "PA13_18") (pintype "bidirectional"))
    )
    (net (code "41") (name "unconnected-(U1-PA14-Pad19)") (class "Default")
      (node (ref "U1") (pin "19") (pinfunction "PA14_19") (pintype "bidirectional"))
    )
    (net (code "42") (name "unconnected-(U1-PB3-Pad9)") (class "Default")
      (node (ref "U1") (pin "9") (pinfunction "PB3_9") (pintype "bidirectional"))
    )
    (net (code "43") (name "unconnected-(U1-PB4-Pad10)") (class "Default")
      (node (ref "U1") (pin "10") (pinfunction "PB4_10") (pintype "bidirectional"))
    )
    (net (code "44") (name "unconnected-(U1-PB5-Pad11)") (class "Default")
      (node (ref "U1") (pin "11") (pinfunction "PB5_11") (pintype "bidirectional"))
    )
    (net (code "45") (name "unconnected-(U1-PB6-Pad12)") (class "Default")
      (node (ref "U1") (pin "12") (pinfunction "PB6_12") (pintype "bidirectional"))
    )
    (net (code "46") (name "unconnected-(U1-PB7-Pad15)") (class "Default")
      (node (ref "U1") (pin "15") (pinfunction "PB7_15") (pintype "bidirectional"))
    )
    (net (code "47") (name "unconnected-(U1-PB8-Pad16)") (class "Default")
      (node (ref "U1") (pin "16") (pinfunction "PB8_16") (pintype "bidirectional"))
    )
    (net (code "48") (name "unconnected-(U1-PB11-Pad21)") (class "Default")
      (node (ref "U1") (pin "21") (pinfunction "PB11_21") (pintype "bidirectional"))
    )
    (net (code "49") (name "unconnected-(U1-PB13-Pad24)") (class "Default")
      (node (ref "U1") (pin "24") (pinfunction "PB13_24") (pintype "bidirectional"))
    )
    (net (code "50") (name "unconnected-(U1-PB14-Pad25)") (class "Default")
      (node (ref "U1") (pin "25") (pinfunction "PB14_25") (pintype "bidirectional"))
    )
    (net (code "51") (name "unconnected-(U1-PC4-Pad13)") (class "Default")
      (node (ref "U1") (pin "13") (pinfunction "PC4_13") (pintype "bidirectional"))
    )
    (net (code "52") (name "unconnected-(U1-PC5-Pad14)") (class "Default")
      (node (ref "U1") (pin "14") (pinfunction "PC5_14") (pintype "bidirectional"))
    )
    (net (code "53") (name "unconnected-(U1-PC6-Pad37)") (class "Default")
      (node (ref "U1") (pin "37") (pinfunction "PC6_37") (pintype "bidirectional"))
    )
    (net (code "54") (name "unconnected-(U1-PC7-Pad38)") (class "Default")
      (node (ref "U1") (pin "38") (pinfunction "PC7_38") (pintype "bidirectional"))
    )
    (net (code "55") (name "unconnected-(U1-PD0-Pad28)") (class "Default")
      (node (ref "U1") (pin "28") (pinfunction "PD0_28") (pintype "bidirectional"))
    )
    (net (code "56") (name "unconnected-(U1-PD1-Pad29)") (class "Default")
      (node (ref "U1") (pin "29") (pinfunction "PD1_29") (pintype "bidirectional"))
    )
    (net (code "57") (name "unconnected-(U1-PD2-Pad30)") (class "Default")
      (node (ref "U1") (pin "30") (pinfunction "PD2_30") (pintype "bidirectional"))
    )
    (net (code "58") (name "unconnected-(U1-PD3-Pad31)") (class "Default")
      (node (ref "U1") (pin "31") (pinfunction "PD3_31") (pintype "bidirectional"))
    )
    (net (code "59") (name "unconnected-(U1-PD4-Pad32)") (class "Default")
      (node (ref "U1") (pin "32") (pinfunction "PD4_32") (pintype "bidirectional"))
    )
    (net (code "60") (name "unconnected-(U1-PD5-Pad33)") (class "Default")
      (node (ref "U1") (pin "33") (pinfunction "PD5_33") (pintype "bidirectional"))
    )
    (net (code "61") (name "unconnected-(U1-PD6-Pad34)") (class "Default")
      (node (ref "U1") (pin "34") (pinfunction "PD6_34") (pintype "bidirectional"))
    )
    (net (code "62") (name "unconnected-(U1-PD7-Pad35)") (class "Default")
      (node (ref "U1") (pin "35") (pinfunction "PD7_35") (pintype "bidirectional"))
    )
    (net (code "63") (name "unconnected-(U1-PD8-Pad36)") (class "Default")
      (node (ref "U1") (pin "36") (pinfunction "PD8_36") (pintype "bidirectional"))
    )
    (net (code "64") (name "unconnected-(U1-PE4-Pad41)") (class "Default")
      (node (ref "U1") (pin "41") (pinfunction "PE4_41") (pintype "bidirectional"))
    )
    (net (code "65") (name "unconnected-(U1-PE5-Pad42)") (class "Default")
      (node (ref "U1") (pin "42") (pinfunction "PE5_42") (pintype "bidirectional"))
    )
    (net (code "66") (name "unconnected-(U1-PE6-Pad43)") (class "Default")
      (node (ref "U1") (pin "43") (pinfunction "PE6_43") (pintype "bidirectional"))
    )
    (net (code "67") (name "unconnected-(U1-PE7-Pad44)") (class "Default")
      (node (ref "U1") (pin "44") (pinfunction "PE7_44") (pintype "bidirectional"))
    )
    (net (code "68") (name "unconnected-(U1-PE8-Pad57)") (class "Default")
      (node (ref "U1") (pin "57") (pinfunction "PE8_57") (pintype "bidirectional"))
    )
    (net (code "69") (name "unconnected-(U1-PE9-Pad58)") (class "Default")
      (node (ref "U1") (pin "58") (pinfunction "PE9_58") (pintype "bidirectional"))
    )
    (net (code "70") (name "unconnected-(U1-PE10-Pad59)") (class "Default")
      (node (ref "U1") (pin "59") (pinfunction "PE10_59") (pintype "bidirectional"))
    )
    (net (code "71") (name "unconnected-(U1-PE11-Pad60)") (class "Default")
      (node (ref "U1") (pin "60") (pinfunction "PE11_60") (pintype "bidirectional"))
    )
    (net (code "72") (name "unconnected-(U1-PE12-Pad61)") (class "Default")
      (node (ref "U1") (pin "61") (pinfunction "PE12_61") (pintype "bidirectional"))
    )
    (net (code "73") (name "unconnected-(U1-PE13-Pad62)") (class "Default")
      (node (ref "U1") (pin "62") (pinfunction "PE13_62") (pintype "bidirectional"))
    )
    (net (code "74") (name "unconnected-(U1-PE14-Pad63)") (class "Default")
      (node (ref "U1") (pin "63") (pinfunction "PE14_63") (pintype "bidirectional"))
    )
    (net (code "75") (name "unconnected-(U1-PE15-Pad64)") (class "Default")
      (node (ref "U1") (pin "64") (pinfunction "PE15_64") (pintype "bidirectional"))
    )
    (net (code "76") (name "unconnected-(U1-PF5-Pad54)") (class "Default")
      (node (ref "U1") (pin "54") (pinfunction "PF5_54") (pintype "bidirectional"))
    )
    (net (code "77") (name "unconnected-(U1-PF12-Pad53)") (class "Default")
      (node (ref "U1") (pin "53") (pinfunction "PF12_53") (pintype "bidirectional"))
    )
    (net (code "78") (name "unconnected-(U2-ADDR-Pad16)") (class "Default")
      (node (ref "U2") (pin "16") (pinfunction "ADDR_16") (pintype "bidirectional"))
    )
    (net (code "79") (name "unconnected-(U2-ALERT1-Pad11)") (class "Default")
      (node (ref "U2") (pin "11") (pinfunction "ALERT1_11") (pintype "bidirectional"))
    )
    (net (code "80") (name "unconnected-(U2-ALERT2-Pad12)") (class "Default")
      (node (ref "U2") (pin "12") (pinfunction "ALERT2_12") (pintype "bidirectional"))
    )
    (net (code "81") (name "unconnected-(U2-ALERT3-Pad14)") (class "Default")
      (node (ref "U2") (pin "14") (pinfunction "ALERT3_14") (pintype "bidirectional"))
    )
    (net (code "82") (name "unconnected-(U2-ALERT4-Pad15)") (class "Default")
      (node (ref "U2") (pin "15") (pinfunction "ALERT4_15") (pintype "bidirectional"))
    )
    (net (code "83") (name "unconnected-(U2-OCALERT-Pad9)") (class "Default")
      (node (ref "U2") (pin "9") (pinfunction "OCALERT_9") (pintype "bidirectional"))
    )
    (net (code "84") (name "unconnected-(U2-SCALERT-Pad7)") (class "Default")
      (node (ref "U2") (pin "7") (pinfunction "SCALERT_7") (pintype "bidirectional"))
    )
    (net (code "85") (name "unconnected-(U2-SCL-Pad19)") (class "Default")
      (node (ref "U2") (pin "19") (pinfunction "SCL_19") (pintype "bidirectional"))
    )
    (net (code "86") (name "unconnected-(U2-SDA-Pad20)") (class "Default")
      (node (ref "U2") (pin "20") (pinfunction "SDA_20") (pintype "bidirectional"))
    )
    (net (code "87") (name "unconnected-(U4-C-Pad4)") (class "Default")
      (node (ref "U4") (pin "4") (pinfunction "C_4") (pintype "bidirectional"))
    )
    (net (code "88") (name "~{RESET}") (class "Default")
      (node (ref "R113") (pin "1") (pinfunction "1_1") (pintype "passive"))
      (node (ref "TC101") (pin "10") (pinfunction "S_10") (pintype "passive"))
      (node (ref "U1") (pin "20") (pinfunction "~{RESET}_20") (pintype "bidirectional"))
    )
  )
)
